# Sheet1.net
KiCad netlist of a schematic drawn in Altium Designer
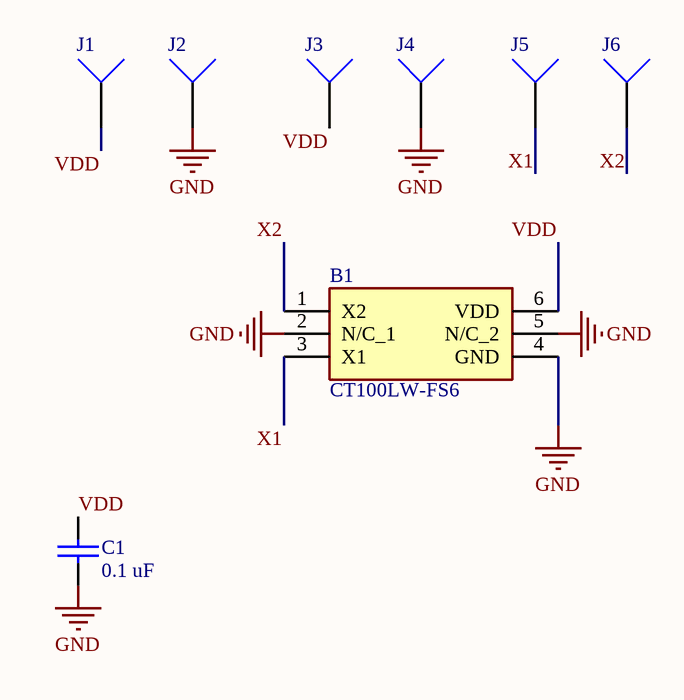
[diagram p0: Sheet1.SchDoc]

(export (version "E")
  (design (tool "Eeschema 10.0.6"))
  (components
    (comp (ref "B1")
      (value "CT100LW-FS6")
      (footprint "SOT95P280X135-6N")
      (libsource (lib "CT100LW-FS6") (part "CT100LW-FS6"))
    )
    (comp (ref "C1")
      (value "0.1 uF")
      (footprint "ece-RAD0.2")
      (description "Capacitor Non Polarised Through Hole")
      (libsource (lib "ece components") (part "CAP"))
    )
    (comp (ref "J1")
      (value "Test pin")
      (footprint "ece-HDR1")
      (description "Socket")
      (fields (field (name "PUBLISHER") "Altium Limited"))
      (libsource (lib "ece components") (part "Test pin"))
    )
    (comp (ref "J2")
      (value "Test pin")
      (footprint "ece-HDR1")
      (description "Socket")
      (fields (field (name "PUBLISHER") "Altium Limited"))
      (libsource (lib "ece components") (part "Test pin"))
    )
    (comp (ref "J3")
      (value "Test pin")
      (footprint "ece-HDR1")
      (description "Socket")
      (fields (field (name "PUBLISHER") "Altium Limited"))
      (libsource (lib "ece components") (part "Test pin"))
    )
    (comp (ref "J4")
      (value "Test pin")
      (footprint "ece-HDR1")
      (description "Socket")
      (fields (field (name "PUBLISHER") "Altium Limited"))
      (libsource (lib "ece components") (part "Test pin"))
    )
    (comp (ref "J5")
      (value "Test pin")
      (footprint "ece-HDR1")
      (description "Socket")
      (fields (field (name "PUBLISHER") "Altium Limited"))
      (libsource (lib "ece components") (part "Test pin"))
    )
    (comp (ref "J6")
      (value "Test pin")
      (footprint "ece-HDR1")
      (description "Socket")
      (fields (field (name "PUBLISHER") "Altium Limited"))
      (libsource (lib "ece components") (part "Test pin"))
    )
  )
  (nets
    (net (code "1") (name "/VDD") (class "Default")
      (node (ref "B1") (pin "6") (pinfunction "VDD_6") (pintype "passive"))
      (node (ref "C1") (pin "1") (pinfunction "1_1") (pintype "passive"))
      (node (ref "J1") (pin "1") (pinfunction "1_1") (pintype "passive"))
      (node (ref "J3") (pin "1") (pinfunction "1_1") (pintype "passive"))
    )
    (net (code "2") (name "/X1") (class "Default")
      (node (ref "B1") (pin "3") (pinfunction "X1_3") (pintype "passive"))
      (node (ref "J5") (pin "1") (pinfunction "1_1") (pintype "passive"))
    )
    (net (code "3") (name "/X2") (class "Default")
      (node (ref "B1") (pin "1") (pinfunction "X2_1") (pintype "passive"))
      (node (ref "J6") (pin "1") (pinfunction "1_1") (pintype "passive"))
    )
    (net (code "4") (name "GND") (class "Default")
      (node (ref "B1") (pin "2") (pinfunction "N/C_1_2") (pintype "passive"))
      (node (ref "B1") (pin "4") (pinfunction "GND_4") (pintype "passive"))
      (node (ref "B1") (pin "5") (pinfunction "N/C_2_5") (pintype "passive"))
      (node (ref "C1") (pin "2") (pinfunction "2_2") (pintype "passive"))
      (node (ref "J2") (pin "1") (pinfunction "1_1") (pintype "passive"))
      (node (ref "J4") (pin "1") (pinfunction "1_1") (pintype "passive"))
    )
  )
)
